# NE555SingleTimer.net
KiCad netlist of a schematic drawn in EAGLE
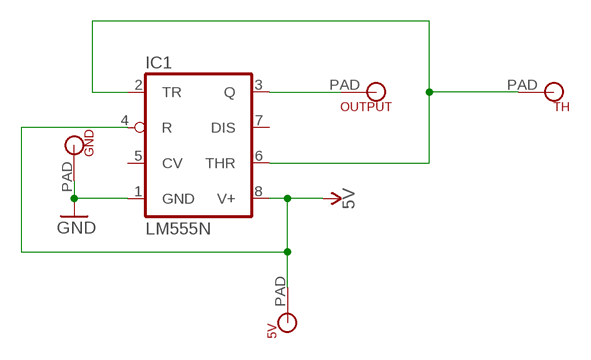
[diagram p0: schematic, sheet 1]

(export (version "E")
  (design (tool "Eeschema 10.0.6"))
  (components
    (comp (ref "5V")
      (value "MICROBIT_PAD")
      (footprint "eagle-import:MICROBIT_PAD")
      (libsource (lib "eagle-import") (part "MICROBIT_PAD"))
    )
    (comp (ref "GND")
      (value "MICROBIT_PAD")
      (footprint "eagle-import:MICROBIT_PAD")
      (libsource (lib "eagle-import") (part "MICROBIT_PAD"))
    )
    (comp (ref "IC1")
      (value "LM555N")
      (footprint "eagle-import:DIL08")
      (libsource (lib "eagle-import") (part "555NLM"))
    )
    (comp (ref "OUTPUT")
      (value "MICROBIT_PAD")
      (footprint "eagle-import:MICROBIT_PAD")
      (libsource (lib "eagle-import") (part "MICROBIT_PAD"))
    )
    (comp (ref "TH")
      (value "MICROBIT_PAD")
      (footprint "eagle-import:MICROBIT_PAD")
      (libsource (lib "eagle-import") (part "MICROBIT_PAD"))
    )
  )
  (nets
    (net (code "1") (name "5V") (class "Default")
      (node (ref "5V") (pin "PAD") (pinfunction "P$1_PAD") (pintype "bidirectional"))
      (node (ref "IC1") (pin "4") (pinfunction "R_4") (pintype "input"))
      (node (ref "IC1") (pin "8") (pinfunction "V+_8") (pintype "power_in"))
    )
    (net (code "2") (name "GND") (class "Default")
      (node (ref "GND") (pin "PAD") (pinfunction "P$1_PAD") (pintype "bidirectional"))
      (node (ref "IC1") (pin "1") (pinfunction "GND_1") (pintype "power_in"))
    )
    (net (code "3") (name "Net-(IC1-Q)") (class "Default")
      (node (ref "IC1") (pin "3") (pinfunction "Q_3") (pintype "output"))
      (node (ref "OUTPUT") (pin "PAD") (pinfunction "P$1_PAD") (pintype "bidirectional"))
    )
    (net (code "4") (name "Net-(IC1-THR)") (class "Default")
      (node (ref "IC1") (pin "2") (pinfunction "TR_2") (pintype "input"))
      (node (ref "IC1") (pin "6") (pinfunction "THR_6") (pintype "input"))
      (node (ref "TH") (pin "PAD") (pinfunction "P$1_PAD") (pintype "bidirectional"))
    )
    (net (code "5") (name "unconnected-(IC1-CV-Pad5)") (class "Default")
      (node (ref "IC1") (pin "5") (pinfunction "CV_5") (pintype "input"))
    )
    (net (code "6") (name "unconnected-(IC1-DIS-Pad7)") (class "Default")
      (node (ref "IC1") (pin "7") (pinfunction "DIS_7") (pintype "input"))
    )
  )
)
